# controle_bt.net
KiCad netlist of a schematic drawn in EAGLE
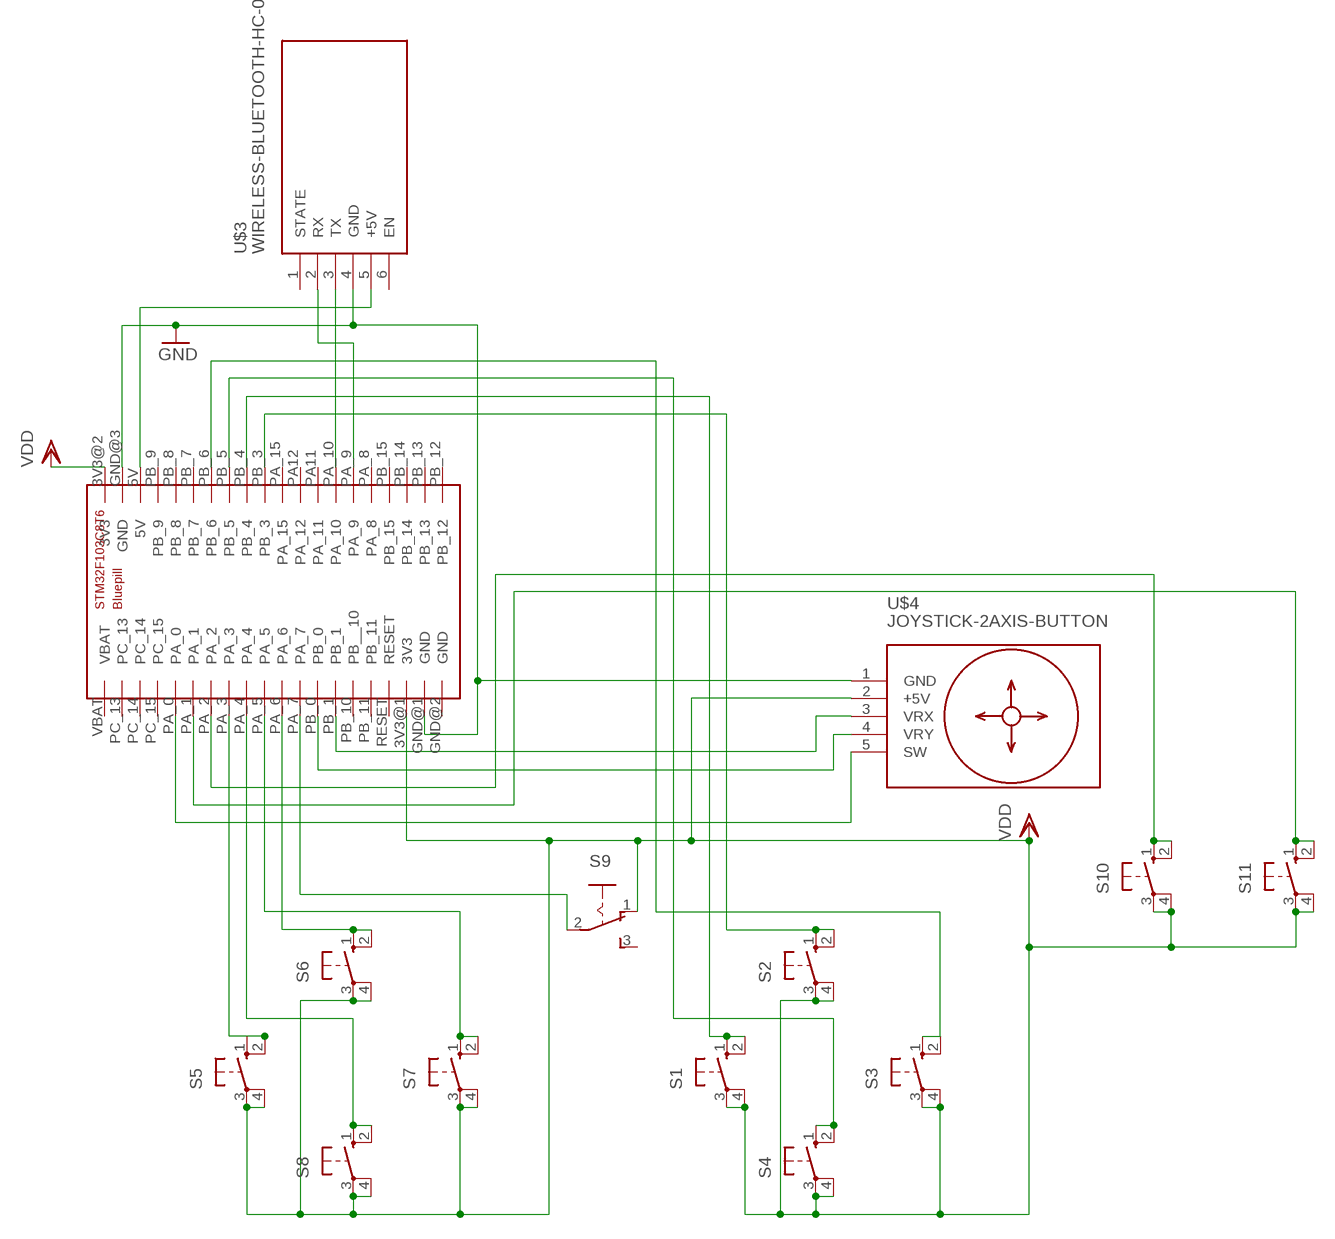
[diagram p0: schematic, sheet 1]

(export (version "E")
  (design (tool "Eeschema 10.0.6"))
  (components
    (comp (ref "S1")
      (value "10-XX")
      (footprint "eagle-import:B3F-10XX")
      (fields (field (name "MPN") "B3F-1000"))
      (libsource (lib "eagle-import") (part "10-XX"))
    )
    (comp (ref "S2")
      (value "10-XX")
      (footprint "eagle-import:B3F-10XX")
      (fields (field (name "MPN") "B3F-1000"))
      (libsource (lib "eagle-import") (part "10-XX"))
    )
    (comp (ref "S3")
      (value "10-XX")
      (footprint "eagle-import:B3F-10XX")
      (fields (field (name "MPN") "B3F-1000"))
      (libsource (lib "eagle-import") (part "10-XX"))
    )
    (comp (ref "S4")
      (value "10-XX")
      (footprint "eagle-import:B3F-10XX")
      (fields (field (name "MPN") "B3F-1000"))
      (libsource (lib "eagle-import") (part "10-XX"))
    )
    (comp (ref "S5")
      (value "10-XX")
      (footprint "eagle-import:B3F-10XX")
      (fields (field (name "MPN") "B3F-1000"))
      (libsource (lib "eagle-import") (part "10-XX"))
    )
    (comp (ref "S6")
      (value "10-XX")
      (footprint "eagle-import:B3F-10XX")
      (fields (field (name "MPN") "B3F-1000"))
      (libsource (lib "eagle-import") (part "10-XX"))
    )
    (comp (ref "S7")
      (value "10-XX")
      (footprint "eagle-import:B3F-10XX")
      (fields (field (name "MPN") "B3F-1000"))
      (libsource (lib "eagle-import") (part "10-XX"))
    )
    (comp (ref "S8")
      (value "10-XX")
      (footprint "eagle-import:B3F-10XX")
      (fields (field (name "MPN") "B3F-1000"))
      (libsource (lib "eagle-import") (part "10-XX"))
    )
    (comp (ref "S9")
      (value "255SB")
      (footprint "eagle-import:255SB")
      (libsource (lib "eagle-import") (part "255SB"))
    )
    (comp (ref "S10")
      (value "10-XX")
      (footprint "eagle-import:B3F-10XX")
      (fields (field (name "MPN") "B3F-1000"))
      (libsource (lib "eagle-import") (part "10-XX"))
    )
    (comp (ref "S11")
      (value "10-XX")
      (footprint "eagle-import:B3F-10XX")
      (fields (field (name "MPN") "B3F-1000"))
      (libsource (lib "eagle-import") (part "10-XX"))
    )
    (comp (ref "U$2")
      (value "STM32_BLUEPILL")
      (footprint "eagle-import:STM32_BLUEPILL")
      (libsource (lib "eagle-import") (part "STM32_BLUEPILL"))
    )
    (comp (ref "U$3")
      (value "WIRELESS-BLUETOOTH-HC-05")
      (footprint "eagle-import:WIRELESS-BLUETOOTH-HC-05")
      (libsource (lib "eagle-import") (part "WIRELESS-BLUETOOTH-HC-05"))
    )
    (comp (ref "U$4")
      (value "JOYSTICK-2AXIS-BUTTON")
      (footprint "eagle-import:JOYSTICK-2AXIS-BUTTON")
      (libsource (lib "eagle-import") (part "JOYSTICK-2AXIS-BUTTON"))
    )
  )
  (nets
    (net (code "1") (name "GND") (class "Default")
      (node (ref "U$2") (pin "GND@1") (pinfunction "GND_GND@1") (pintype "bidirectional"))
      (node (ref "U$2") (pin "GND@3") (pinfunction "GND_GND@3") (pintype "bidirectional"))
      (node (ref "U$3") (pin "4") (pinfunction "GND_4") (pintype "power_in"))
      (node (ref "U$4") (pin "1") (pinfunction "GND_1") (pintype "power_in"))
    )
    (net (code "2") (name "Net-(S1-S)") (class "Default")
      (node (ref "S1") (pin "1") (pinfunction "S_1") (pintype "passive"))
      (node (ref "S1") (pin "2") (pinfunction "S1_2") (pintype "passive"))
      (node (ref "U$2") (pin "PB_4") (pinfunction "PB_4_PB_4") (pintype "bidirectional"))
    )
    (net (code "3") (name "Net-(S2-S)") (class "Default")
      (node (ref "S2") (pin "1") (pinfunction "S_1") (pintype "passive"))
      (node (ref "S2") (pin "2") (pinfunction "S1_2") (pintype "passive"))
      (node (ref "U$2") (pin "PB_3") (pinfunction "PB_3_PB_3") (pintype "bidirectional"))
    )
    (net (code "4") (name "Net-(S3-S)") (class "Default")
      (node (ref "S3") (pin "1") (pinfunction "S_1") (pintype "passive"))
      (node (ref "S3") (pin "2") (pinfunction "S1_2") (pintype "passive"))
      (node (ref "U$2") (pin "PB_6") (pinfunction "PB_6_PB_6") (pintype "bidirectional"))
    )
    (net (code "5") (name "Net-(S4-S)") (class "Default")
      (node (ref "S4") (pin "1") (pinfunction "S_1") (pintype "passive"))
      (node (ref "S4") (pin "2") (pinfunction "S1_2") (pintype "passive"))
      (node (ref "U$2") (pin "PB_5") (pinfunction "PB_5_PB_5") (pintype "bidirectional"))
    )
    (net (code "6") (name "Net-(S5-S)") (class "Default")
      (node (ref "S5") (pin "1") (pinfunction "S_1") (pintype "passive"))
      (node (ref "S5") (pin "2") (pinfunction "S1_2") (pintype "passive"))
      (node (ref "U$2") (pin "PA_3") (pinfunction "PA_3_PA_3") (pintype "bidirectional"))
    )
    (net (code "7") (name "Net-(S6-S)") (class "Default")
      (node (ref "S6") (pin "1") (pinfunction "S_1") (pintype "passive"))
      (node (ref "S6") (pin "2") (pinfunction "S1_2") (pintype "passive"))
      (node (ref "U$2") (pin "PA_6") (pinfunction "PA_6_PA_6") (pintype "bidirectional"))
    )
    (net (code "8") (name "Net-(S7-S)") (class "Default")
      (node (ref "S7") (pin "1") (pinfunction "S_1") (pintype "passive"))
      (node (ref "S7") (pin "2") (pinfunction "S1_2") (pintype "passive"))
      (node (ref "U$2") (pin "PA_5") (pinfunction "PA_5_PA_5") (pintype "bidirectional"))
    )
    (net (code "9") (name "Net-(S8-S)") (class "Default")
      (node (ref "S8") (pin "1") (pinfunction "S_1") (pintype "passive"))
      (node (ref "S8") (pin "2") (pinfunction "S1_2") (pintype "passive"))
      (node (ref "U$2") (pin "PA_4") (pinfunction "PA_4_PA_4") (pintype "bidirectional"))
    )
    (net (code "10") (name "Net-(S9-P)") (class "Default")
      (node (ref "S9") (pin "2") (pinfunction "P_2") (pintype "passive"))
      (node (ref "U$2") (pin "PA_7") (pinfunction "PA_7_PA_7") (pintype "bidirectional"))
    )
    (net (code "11") (name "Net-(S10-S)") (class "Default")
      (node (ref "S10") (pin "1") (pinfunction "S_1") (pintype "passive"))
      (node (ref "S10") (pin "2") (pinfunction "S1_2") (pintype "passive"))
      (node (ref "U$2") (pin "PA_2") (pinfunction "PA_2_PA_2") (pintype "bidirectional"))
    )
    (net (code "12") (name "Net-(S11-S)") (class "Default")
      (node (ref "S11") (pin "1") (pinfunction "S_1") (pintype "passive"))
      (node (ref "S11") (pin "2") (pinfunction "S1_2") (pintype "passive"))
      (node (ref "U$2") (pin "PA_1") (pinfunction "PA_1_PA_1") (pintype "bidirectional"))
    )
    (net (code "13") (name "Net-(U$3-+5V)") (class "Default")
      (node (ref "U$2") (pin "5V") (pinfunction "5V_5V") (pintype "bidirectional"))
      (node (ref "U$3") (pin "5") (pinfunction "+5V_5") (pintype "power_in"))
    )
    (net (code "14") (name "Net-(U$3-RX)") (class "Default")
      (node (ref "U$2") (pin "PA_9") (pinfunction "PA_9_PA_9") (pintype "bidirectional"))
      (node (ref "U$3") (pin "2") (pinfunction "RX_2") (pintype "bidirectional"))
    )
    (net (code "15") (name "Net-(U$3-TX)") (class "Default")
      (node (ref "U$2") (pin "PA_10") (pinfunction "PA_10_PA_10") (pintype "bidirectional"))
      (node (ref "U$3") (pin "3") (pinfunction "TX_3") (pintype "bidirectional"))
    )
    (net (code "16") (name "Net-(U$4-SW)") (class "Default")
      (node (ref "U$2") (pin "PA_0") (pinfunction "PA_0_PA_0") (pintype "bidirectional"))
      (node (ref "U$4") (pin "5") (pinfunction "SW_5") (pintype "passive"))
    )
    (net (code "17") (name "Net-(U$4-VRX)") (class "Default")
      (node (ref "U$2") (pin "PB_1") (pinfunction "PB_1_PB_1") (pintype "bidirectional"))
      (node (ref "U$4") (pin "3") (pinfunction "VRX_3") (pintype "passive"))
    )
    (net (code "18") (name "Net-(U$4-VRY)") (class "Default")
      (node (ref "U$2") (pin "PB_0") (pinfunction "PB_0_PB_0") (pintype "bidirectional"))
      (node (ref "U$4") (pin "4") (pinfunction "VRY_4") (pintype "passive"))
    )
    (net (code "19") (name "VDD") (class "Default")
      (node (ref "S1") (pin "3") (pinfunction "P_3") (pintype "passive"))
      (node (ref "S1") (pin "4") (pinfunction "P1_4") (pintype "passive"))
      (node (ref "S10") (pin "3") (pinfunction "P_3") (pintype "passive"))
      (node (ref "S10") (pin "4") (pinfunction "P1_4") (pintype "passive"))
      (node (ref "S11") (pin "3") (pinfunction "P_3") (pintype "passive"))
      (node (ref "S11") (pin "4") (pinfunction "P1_4") (pintype "passive"))
      (node (ref "S2") (pin "3") (pinfunction "P_3") (pintype "passive"))
      (node (ref "S2") (pin "4") (pinfunction "P1_4") (pintype "passive"))
      (node (ref "S3") (pin "3") (pinfunction "P_3") (pintype "passive"))
      (node (ref "S3") (pin "4") (pinfunction "P1_4") (pintype "passive"))
      (node (ref "S4") (pin "3") (pinfunction "P_3") (pintype "passive"))
      (node (ref "S4") (pin "4") (pinfunction "P1_4") (pintype "passive"))
      (node (ref "S5") (pin "3") (pinfunction "P_3") (pintype "passive"))
      (node (ref "S5") (pin "4") (pinfunction "P1_4") (pintype "passive"))
      (node (ref "S6") (pin "3") (pinfunction "P_3") (pintype "passive"))
      (node (ref "S6") (pin "4") (pinfunction "P1_4") (pintype "passive"))
      (node (ref "S7") (pin "3") (pinfunction "P_3") (pintype "passive"))
      (node (ref "S7") (pin "4") (pinfunction "P1_4") (pintype "passive"))
      (node (ref "S8") (pin "3") (pinfunction "P_3") (pintype "passive"))
      (node (ref "S8") (pin "4") (pinfunction "P1_4") (pintype "passive"))
      (node (ref "S9") (pin "1") (pinfunction "O_1") (pintype "passive"))
      (node (ref "U$2") (pin "3V3@1") (pinfunction "3V3_3V3@1") (pintype "bidirectional"))
      (node (ref "U$2") (pin "3V3@2") (pinfunction "3V3_3V3@2") (pintype "bidirectional"))
      (node (ref "U$4") (pin "2") (pinfunction "+5V_2") (pintype "power_in"))
    )
    (net (code "20") (name "unconnected-(S9-S-Pad3)") (class "Default")
      (node (ref "S9") (pin "3") (pinfunction "S_3") (pintype "passive"))
    )
    (net (code "21") (name "unconnected-(U$2-GND-PadGND@2)") (class "Default")
      (node (ref "U$2") (pin "GND@2") (pinfunction "GND_GND@2") (pintype "bidirectional"))
    )
    (net (code "22") (name "unconnected-(U$2-PA_11-PadPA11)") (class "Default")
      (node (ref "U$2") (pin "PA11") (pinfunction "PA_11_PA11") (pintype "bidirectional"))
    )
    (net (code "23") (name "unconnected-(U$2-PA_12-PadPA12)") (class "Default")
      (node (ref "U$2") (pin "PA12") (pinfunction "PA_12_PA12") (pintype "bidirectional"))
    )
    (net (code "24") (name "unconnected-(U$2-PB__10-PadPB_10)") (class "Default")
      (node (ref "U$2") (pin "PB_10") (pinfunction "PB__10_PB_10") (pintype "bidirectional"))
    )
    (net (code "25") (name "unconnected-(U$2-PadPA_8)") (class "Default")
      (node (ref "U$2") (pin "PA_8") (pinfunction "PA_8_PA_8") (pintype "bidirectional"))
    )
    (net (code "26") (name "unconnected-(U$2-PadPA_15)") (class "Default")
      (node (ref "U$2") (pin "PA_15") (pinfunction "PA_15_PA_15") (pintype "bidirectional"))
    )
    (net (code "27") (name "unconnected-(U$2-PadPB_7)") (class "Default")
      (node (ref "U$2") (pin "PB_7") (pinfunction "PB_7_PB_7") (pintype "bidirectional"))
    )
    (net (code "28") (name "unconnected-(U$2-PadPB_8)") (class "Default")
      (node (ref "U$2") (pin "PB_8") (pinfunction "PB_8_PB_8") (pintype "bidirectional"))
    )
    (net (code "29") (name "unconnected-(U$2-PadPB_9)") (class "Default")
      (node (ref "U$2") (pin "PB_9") (pinfunction "PB_9_PB_9") (pintype "bidirectional"))
    )
    (net (code "30") (name "unconnected-(U$2-PadPB_11)") (class "Default")
      (node (ref "U$2") (pin "PB_11") (pinfunction "PB_11_PB_11") (pintype "bidirectional"))
    )
    (net (code "31") (name "unconnected-(U$2-PadPB_12)") (class "Default")
      (node (ref "U$2") (pin "PB_12") (pinfunction "PB_12_PB_12") (pintype "bidirectional"))
    )
    (net (code "32") (name "unconnected-(U$2-PadPB_13)") (class "Default")
      (node (ref "U$2") (pin "PB_13") (pinfunction "PB_13_PB_13") (pintype "bidirectional"))
    )
    (net (code "33") (name "unconnected-(U$2-PadPB_14)") (class "Default")
      (node (ref "U$2") (pin "PB_14") (pinfunction "PB_14_PB_14") (pintype "bidirectional"))
    )
    (net (code "34") (name "unconnected-(U$2-PadPB_15)") (class "Default")
      (node (ref "U$2") (pin "PB_15") (pinfunction "PB_15_PB_15") (pintype "bidirectional"))
    )
    (net (code "35") (name "unconnected-(U$2-PadPC_13)") (class "Default")
      (node (ref "U$2") (pin "PC_13") (pinfunction "PC_13_PC_13") (pintype "bidirectional"))
    )
    (net (code "36") (name "unconnected-(U$2-PadPC_14)") (class "Default")
      (node (ref "U$2") (pin "PC_14") (pinfunction "PC_14_PC_14") (pintype "bidirectional"))
    )
    (net (code "37") (name "unconnected-(U$2-PadPC_15)") (class "Default")
      (node (ref "U$2") (pin "PC_15") (pinfunction "PC_15_PC_15") (pintype "bidirectional"))
    )
    (net (code "38") (name "unconnected-(U$2-PadRESET)") (class "Default")
      (node (ref "U$2") (pin "RESET") (pinfunction "RESET_RESET") (pintype "bidirectional"))
    )
    (net (code "39") (name "unconnected-(U$2-PadVBAT)") (class "Default")
      (node (ref "U$2") (pin "VBAT") (pinfunction "VBAT_VBAT") (pintype "bidirectional"))
    )
    (net (code "40") (name "unconnected-(U$3-EN-Pad6)") (class "Default")
      (node (ref "U$3") (pin "6") (pinfunction "EN_6") (pintype "bidirectional"))
    )
    (net (code "41") (name "unconnected-(U$3-STATE-Pad1)") (class "Default")
      (node (ref "U$3") (pin "1") (pinfunction "STATE_1") (pintype "bidirectional"))
    )
  )
)
